# v1_0.net
KiCad netlist of a schematic drawn in Altium Designer
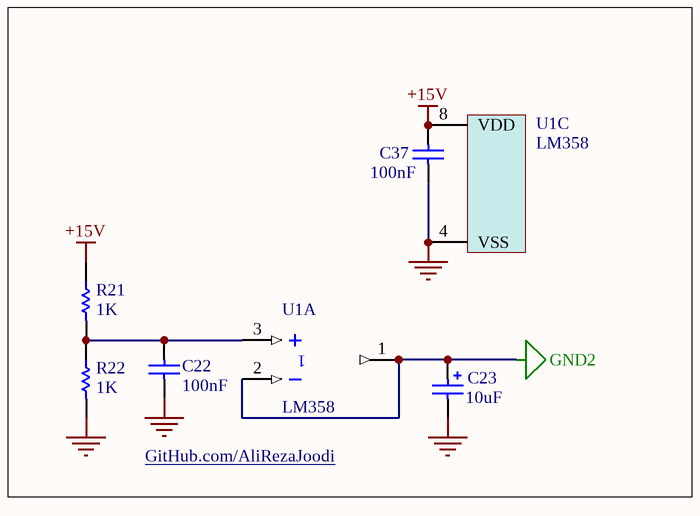
[diagram p0: v1.0.SchDoc]

(export (version "E")
  (design (tool "Eeschema 10.0.6"))
  (components
    (comp (ref "C22")
      (value "100nF")
      (footprint "CAPNTO2.54-3.05x1.78A")
      (description "Capacitor")
      (fields (field (name "MANUFACTURER") "Generic Components") (field (name "PUBLISHER") "Altium Limited"))
      (libsource (lib "Miscellaneous Devices") (part "Cap"))
    )
    (comp (ref "C23")
      (value "10uF")
      (footprint "CAPPR2.5-6.3x5")
      (description "Polarized Capacitor (Radial)")
      (fields (field (name "MANUFACTURER") "Generic Components") (field (name "PUBLISHER") "Altium Limited"))
      (libsource (lib "Miscellaneous Devices") (part "Cap Pol1"))
    )
    (comp (ref "C37")
      (value "100nF")
      (footprint "CAPNTO2.54-3.05x1.78A")
      (description "Capacitor")
      (fields (field (name "MANUFACTURER") "Generic Components") (field (name "PUBLISHER") "Altium Limited"))
      (libsource (lib "Miscellaneous Devices") (part "Cap"))
    )
    (comp (ref "R21")
      (value "1K")
      (footprint "AXIAL-0.4")
      (description "Resistor")
      (fields (field (name "PUBLISHER") "Altium Limited"))
      (libsource (lib "Miscellaneous Devices") (part "Res1"))
    )
    (comp (ref "R22")
      (value "1K")
      (footprint "AXIAL-0.4")
      (description "Resistor")
      (fields (field (name "PUBLISHER") "Altium Limited"))
      (libsource (lib "Miscellaneous Devices") (part "Res1"))
    )
    (comp (ref "U1")
      (value "LM358")
      (footprint "DIP8")
      (description "Dual Low-Power Operational Amplifier")
      (fields (field (name "PUBLISHER") "Altium Limited"))
      (libsource (lib "my Libraries") (part "LM358"))
    )
  )
  (nets
    (net (code "1") (name "+15V") (class "Default")
      (node (ref "C37") (pin "2") (pinfunction "2_2") (pintype "passive"))
      (node (ref "R21") (pin "1") (pinfunction "1_1") (pintype "passive"))
      (node (ref "U1") (pin "8") (pinfunction "VDD_8") (pintype "passive"))
    )
    (net (code "2") (name "GND") (class "Default")
      (node (ref "C22") (pin "1") (pinfunction "1_1") (pintype "passive"))
      (node (ref "C23") (pin "2") (pinfunction "2_2") (pintype "passive"))
      (node (ref "C37") (pin "1") (pinfunction "1_1") (pintype "passive"))
      (node (ref "R22") (pin "2") (pinfunction "2_2") (pintype "passive"))
      (node (ref "U1") (pin "4") (pinfunction "VSS_4") (pintype "power_in"))
    )
    (net (code "3") (name "GND2") (class "Default")
      (node (ref "C23") (pin "1") (pinfunction "1_1") (pintype "passive"))
      (node (ref "U1") (pin "1") (pinfunction "OUT_1") (pintype "output"))
      (node (ref "U1") (pin "2") (pinfunction "IN-_2") (pintype "input"))
    )
    (net (code "4") (name "Net-(U1A-IN+)") (class "Default")
      (node (ref "C22") (pin "2") (pinfunction "2_2") (pintype "passive"))
      (node (ref "R21") (pin "2") (pinfunction "2_2") (pintype "passive"))
      (node (ref "R22") (pin "1") (pinfunction "1_1") (pintype "passive"))
      (node (ref "U1") (pin "3") (pinfunction "IN+_3") (pintype "input"))
    )
  )
)
